# PowerLcd.net
KiCad netlist of a schematic drawn in EAGLE
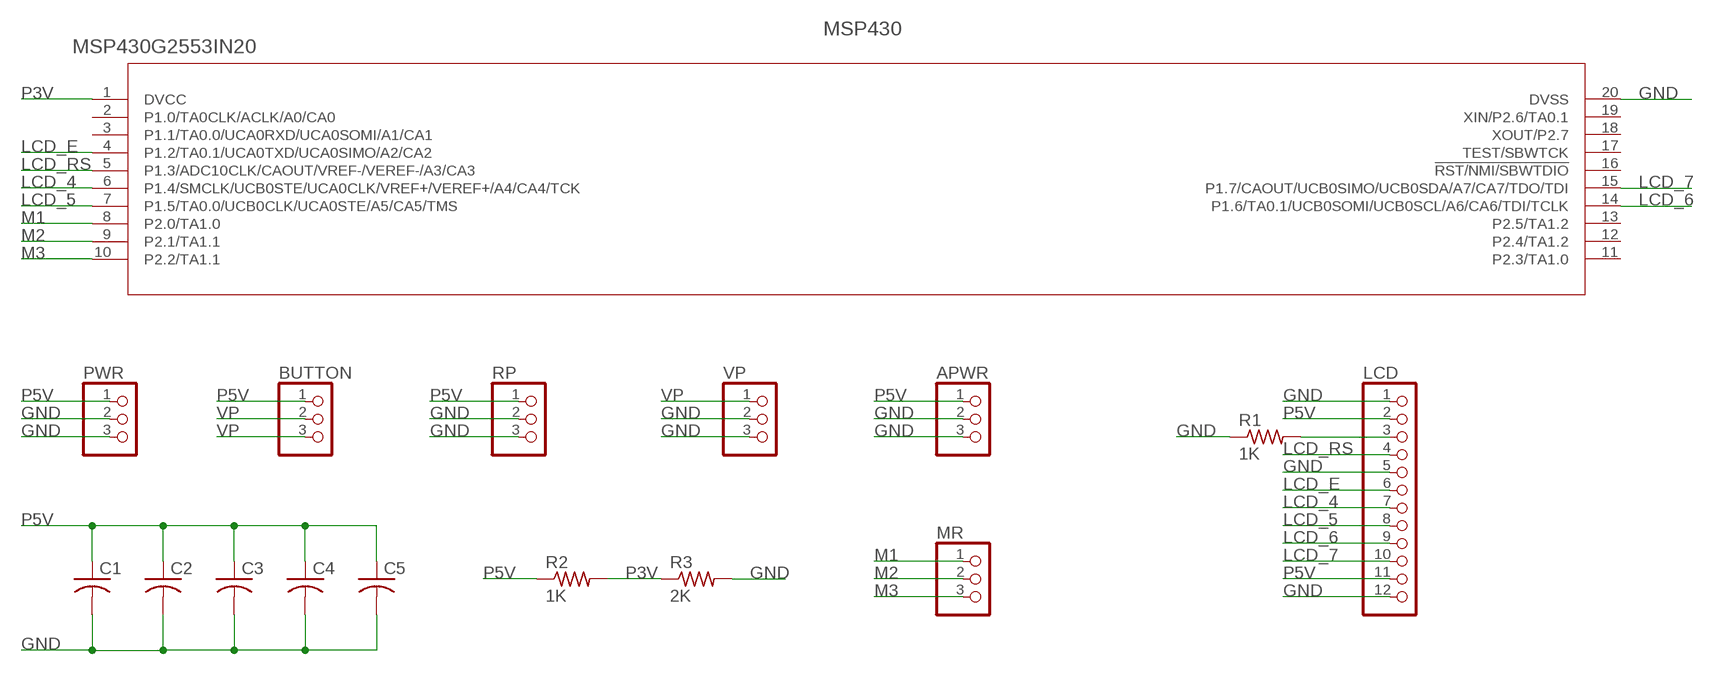
[diagram p0: schematic, sheet 1]

(export (version "E")
  (design (tool "Eeschema 10.0.6"))
  (components
    (comp (ref "APWR")
      (value "PINHD-1X3")
      (footprint "eagle-import:1X03")
      (libsource (lib "eagle-import") (part "PINHD-1X3"))
    )
    (comp (ref "BUTTON")
      (value "PINHD-1X3")
      (footprint "eagle-import:1X03")
      (libsource (lib "eagle-import") (part "PINHD-1X3"))
    )
    (comp (ref "C1")
      (value "C-US075-042X103")
      (footprint "eagle-import:C075-042X103")
      (libsource (lib "eagle-import") (part "C-US075-042X103"))
    )
    (comp (ref "C2")
      (value "C-US075-042X103")
      (footprint "eagle-import:C075-042X103")
      (libsource (lib "eagle-import") (part "C-US075-042X103"))
    )
    (comp (ref "C3")
      (value "C-US075-042X103")
      (footprint "eagle-import:C075-042X103")
      (libsource (lib "eagle-import") (part "C-US075-042X103"))
    )
    (comp (ref "C4")
      (value "C-US075-042X103")
      (footprint "eagle-import:C075-042X103")
      (libsource (lib "eagle-import") (part "C-US075-042X103"))
    )
    (comp (ref "C5")
      (value "C-US075-042X103")
      (footprint "eagle-import:C075-042X103")
      (libsource (lib "eagle-import") (part "C-US075-042X103"))
    )
    (comp (ref "LCD")
      (value "PINHD-1X12")
      (footprint "eagle-import:1X12")
      (libsource (lib "eagle-import") (part "PINHD-1X12"))
    )
    (comp (ref "MR")
      (value "PINHD-1X3")
      (footprint "eagle-import:1X03")
      (libsource (lib "eagle-import") (part "PINHD-1X3"))
    )
    (comp (ref "MSP430")
      (value "MSP430G2553IN20")
      (footprint "eagle-import:N20_TEX")
      (libsource (lib "eagle-import") (part "MSP430G2553IN20"))
    )
    (comp (ref "PWR")
      (value "PINHD-1X3")
      (footprint "eagle-import:1X03")
      (libsource (lib "eagle-import") (part "PINHD-1X3"))
    )
    (comp (ref "R1")
      (value "1K")
      (footprint "eagle-import:0204_5")
      (libsource (lib "eagle-import") (part "R-US_0204/5"))
    )
    (comp (ref "R2")
      (value "1K")
      (footprint "eagle-import:0204_5")
      (libsource (lib "eagle-import") (part "R-US_0204/5"))
    )
    (comp (ref "R3")
      (value "2K")
      (footprint "eagle-import:0204_5")
      (libsource (lib "eagle-import") (part "R-US_0204/5"))
    )
    (comp (ref "RP")
      (value "PINHD-1X3")
      (footprint "eagle-import:1X03")
      (libsource (lib "eagle-import") (part "PINHD-1X3"))
    )
    (comp (ref "VP")
      (value "PINHD-1X3")
      (footprint "eagle-import:1X03")
      (libsource (lib "eagle-import") (part "PINHD-1X3"))
    )
  )
  (nets
    (net (code "1") (name "/GND") (class "Default")
      (node (ref "APWR") (pin "2") (pinfunction "2_2") (pintype "passive"))
      (node (ref "APWR") (pin "3") (pinfunction "3_3") (pintype "passive"))
      (node (ref "C1") (pin "2") (pinfunction "2_2") (pintype "passive"))
      (node (ref "C2") (pin "2") (pinfunction "2_2") (pintype "passive"))
      (node (ref "C3") (pin "2") (pinfunction "2_2") (pintype "passive"))
      (node (ref "C4") (pin "2") (pinfunction "2_2") (pintype "passive"))
      (node (ref "C5") (pin "2") (pinfunction "2_2") (pintype "passive"))
      (node (ref "LCD") (pin "1") (pinfunction "1_1") (pintype "passive"))
      (node (ref "LCD") (pin "12") (pinfunction "12_12") (pintype "passive"))
      (node (ref "LCD") (pin "5") (pinfunction "5_5") (pintype "passive"))
      (node (ref "MSP430") (pin "20") (pinfunction "DVSS_20") (pintype "power_in"))
      (node (ref "PWR") (pin "2") (pinfunction "2_2") (pintype "passive"))
      (node (ref "PWR") (pin "3") (pinfunction "3_3") (pintype "passive"))
      (node (ref "R1") (pin "1") (pinfunction "1_1") (pintype "passive"))
      (node (ref "R3") (pin "2") (pinfunction "2_2") (pintype "passive"))
      (node (ref "RP") (pin "2") (pinfunction "2_2") (pintype "passive"))
      (node (ref "RP") (pin "3") (pinfunction "3_3") (pintype "passive"))
      (node (ref "VP") (pin "2") (pinfunction "2_2") (pintype "passive"))
      (node (ref "VP") (pin "3") (pinfunction "3_3") (pintype "passive"))
    )
    (net (code "2") (name "/LCD_4") (class "Default")
      (node (ref "LCD") (pin "7") (pinfunction "7_7") (pintype "passive"))
      (node (ref "MSP430") (pin "6") (pinfunction "P1.4/SMCLK/UCB0STE/UCA0CLK/VREF+/VEREF+/A4/CA4/TCK_6") (pintype "bidirectional"))
    )
    (net (code "3") (name "/LCD_5") (class "Default")
      (node (ref "LCD") (pin "8") (pinfunction "8_8") (pintype "passive"))
      (node (ref "MSP430") (pin "7") (pinfunction "P1.5/TA0.0/UCB0CLK/UCA0STE/A5/CA5/TMS_7") (pintype "bidirectional"))
    )
    (net (code "4") (name "/LCD_6") (class "Default")
      (node (ref "LCD") (pin "9") (pinfunction "9_9") (pintype "passive"))
      (node (ref "MSP430") (pin "14") (pinfunction "P1.6/TA0.1/UCB0SOMI/UCB0SCL/A6/CA6/TDI/TCLK_14") (pintype "bidirectional"))
    )
    (net (code "5") (name "/LCD_7") (class "Default")
      (node (ref "LCD") (pin "10") (pinfunction "10_10") (pintype "passive"))
      (node (ref "MSP430") (pin "15") (pinfunction "P1.7/CAOUT/UCB0SIMO/UCB0SDA/A7/CA7/TDO/TDI_15") (pintype "bidirectional"))
    )
    (net (code "6") (name "/LCD_E") (class "Default")
      (node (ref "LCD") (pin "6") (pinfunction "6_6") (pintype "passive"))
      (node (ref "MSP430") (pin "4") (pinfunction "P1.2/TA0.1/UCA0TXD/UCA0SIMO/A2/CA2_4") (pintype "bidirectional"))
    )
    (net (code "7") (name "/LCD_RS") (class "Default")
      (node (ref "LCD") (pin "4") (pinfunction "4_4") (pintype "passive"))
      (node (ref "MSP430") (pin "5") (pinfunction "P1.3/ADC10CLK/CAOUT/VREF-/VEREF-/A3/CA3_5") (pintype "bidirectional"))
    )
    (net (code "8") (name "/M1") (class "Default")
      (node (ref "MR") (pin "1") (pinfunction "1_1") (pintype "passive"))
      (node (ref "MSP430") (pin "8") (pinfunction "P2.0/TA1.0_8") (pintype "bidirectional"))
    )
    (net (code "9") (name "/M2") (class "Default")
      (node (ref "MR") (pin "2") (pinfunction "2_2") (pintype "passive"))
      (node (ref "MSP430") (pin "9") (pinfunction "P2.1/TA1.1_9") (pintype "bidirectional"))
    )
    (net (code "10") (name "/M3") (class "Default")
      (node (ref "MR") (pin "3") (pinfunction "3_3") (pintype "passive"))
      (node (ref "MSP430") (pin "10") (pinfunction "P2.2/TA1.1_10") (pintype "bidirectional"))
    )
    (net (code "11") (name "/P3V") (class "Default")
      (node (ref "MSP430") (pin "1") (pinfunction "DVCC_1") (pintype "power_in"))
      (node (ref "R2") (pin "2") (pinfunction "2_2") (pintype "passive"))
      (node (ref "R3") (pin "1") (pinfunction "1_1") (pintype "passive"))
    )
    (net (code "12") (name "/P5V") (class "Default")
      (node (ref "APWR") (pin "1") (pinfunction "1_1") (pintype "passive"))
      (node (ref "BUTTON") (pin "1") (pinfunction "1_1") (pintype "passive"))
      (node (ref "C1") (pin "1") (pinfunction "1_1") (pintype "passive"))
      (node (ref "C2") (pin "1") (pinfunction "1_1") (pintype "passive"))
      (node (ref "C3") (pin "1") (pinfunction "1_1") (pintype "passive"))
      (node (ref "C4") (pin "1") (pinfunction "1_1") (pintype "passive"))
      (node (ref "C5") (pin "1") (pinfunction "1_1") (pintype "passive"))
      (node (ref "LCD") (pin "11") (pinfunction "11_11") (pintype "passive"))
      (node (ref "LCD") (pin "2") (pinfunction "2_2") (pintype "passive"))
      (node (ref "PWR") (pin "1") (pinfunction "1_1") (pintype "passive"))
      (node (ref "R2") (pin "1") (pinfunction "1_1") (pintype "passive"))
      (node (ref "RP") (pin "1") (pinfunction "1_1") (pintype "passive"))
    )
    (net (code "13") (name "/VP") (class "Default")
      (node (ref "BUTTON") (pin "2") (pinfunction "2_2") (pintype "passive"))
      (node (ref "BUTTON") (pin "3") (pinfunction "3_3") (pintype "passive"))
      (node (ref "VP") (pin "1") (pinfunction "1_1") (pintype "passive"))
    )
    (net (code "14") (name "Net-(LCD-Pad3)") (class "Default")
      (node (ref "LCD") (pin "3") (pinfunction "3_3") (pintype "passive"))
      (node (ref "R1") (pin "2") (pinfunction "2_2") (pintype "passive"))
    )
    (net (code "15") (name "unconnected-(MSP430-P1.0{slash}TA0CLK{slash}ACLK{slash}A0{slash}CA0-Pad2)") (class "Default")
      (node (ref "MSP430") (pin "2") (pinfunction "P1.0/TA0CLK/ACLK/A0/CA0_2") (pintype "bidirectional"))
    )
    (net (code "16") (name "unconnected-(MSP430-P1.1{slash}TA0.0{slash}UCA0RXD{slash}UCA0SOMI{slash}A1{slash}CA1-Pad3)") (class "Default")
      (node (ref "MSP430") (pin "3") (pinfunction "P1.1/TA0.0/UCA0RXD/UCA0SOMI/A1/CA1_3") (pintype "bidirectional"))
    )
    (net (code "17") (name "unconnected-(MSP430-P2.3{slash}TA1.0-Pad11)") (class "Default")
      (node (ref "MSP430") (pin "11") (pinfunction "P2.3/TA1.0_11") (pintype "bidirectional"))
    )
    (net (code "18") (name "unconnected-(MSP430-P2.4{slash}TA1.2-Pad12)") (class "Default")
      (node (ref "MSP430") (pin "12") (pinfunction "P2.4/TA1.2_12") (pintype "bidirectional"))
    )
    (net (code "19") (name "unconnected-(MSP430-P2.5{slash}TA1.2-Pad13)") (class "Default")
      (node (ref "MSP430") (pin "13") (pinfunction "P2.5/TA1.2_13") (pintype "bidirectional"))
    )
    (net (code "20") (name "unconnected-(MSP430-TEST{slash}SBWTCK-Pad17)") (class "Default")
      (node (ref "MSP430") (pin "17") (pinfunction "TEST/SBWTCK_17") (pintype "bidirectional"))
    )
    (net (code "21") (name "unconnected-(MSP430-XIN{slash}P2.6{slash}TA0.1-Pad19)") (class "Default")
      (node (ref "MSP430") (pin "19") (pinfunction "XIN/P2.6/TA0.1_19") (pintype "bidirectional"))
    )
    (net (code "22") (name "unconnected-(MSP430-XOUT{slash}P2.7-Pad18)") (class "Default")
      (node (ref "MSP430") (pin "18") (pinfunction "XOUT/P2.7_18") (pintype "bidirectional"))
    )
    (net (code "23") (name "unconnected-(MSP430-~{RST{slash}NMI{slash}SBWTDIO}-Pad16)") (class "Default")
      (node (ref "MSP430") (pin "16") (pinfunction "~{RST/NMI/SBWTDIO}_16") (pintype "bidirectional"))
    )
  )
)
